# motherboard.net
KiCad netlist of a schematic drawn in EAGLE
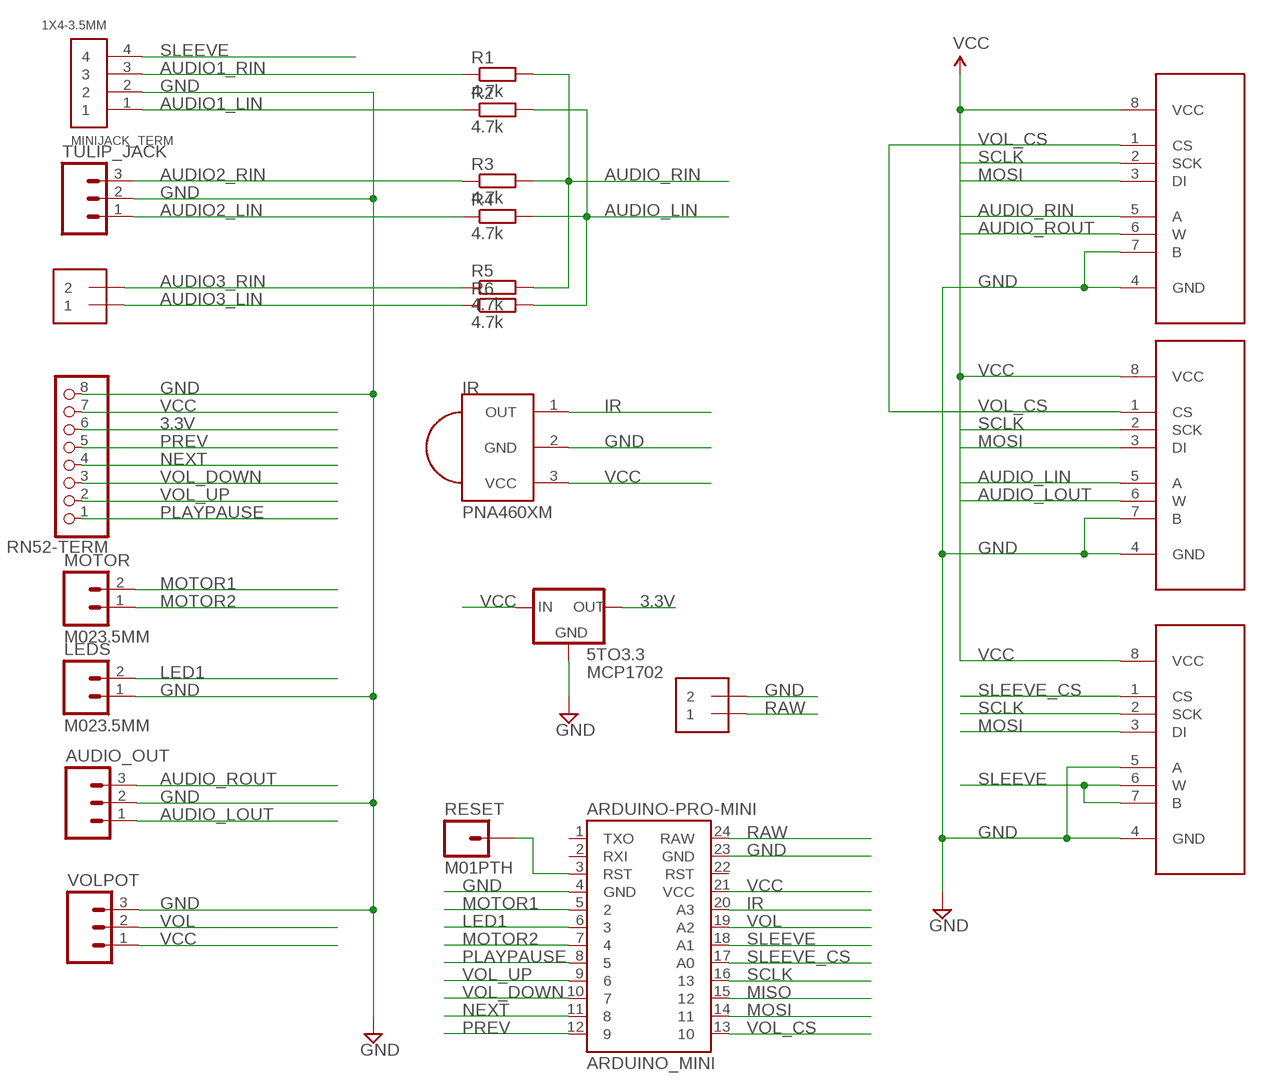
[diagram p0: schematic, sheet 1]

(export (version "E")
  (design (tool "Eeschema 10.0.6"))
  (components
    (comp (ref "5TO3.3")
      (value "MCP1702")
      (footprint "eagle-import:TO92-INLINE")
      (libsource (lib "eagle-import") (part "MCP1700INLINE"))
    )
    (comp (ref "ARDUINO-PRO-MINI")
      (value "ARDUINO_MINI")
      (footprint "eagle-import:ARDUINO_MINI")
      (libsource (lib "eagle-import") (part "ARDUINO_MINI"))
    )
    (comp (ref "AUDIO_OUT")
      (value "M03SCREW")
      (footprint "eagle-import:SCREWTERMINAL-3.5MM-3")
      (libsource (lib "eagle-import") (part "M03SCREW"))
    )
    (comp (ref "BL_AUDIO_TERM")
      (value "1X2-3.5MM")
      (footprint "eagle-import:1X2-3.5MM")
      (libsource (lib "eagle-import") (part "1X2-3.5MM"))
    )
    (comp (ref "DPOT_LFT")
      (value "MCP41XXXDIL")
      (footprint "eagle-import:DIL-08")
      (libsource (lib "eagle-import") (part "MCP41XXXDIL"))
    )
    (comp (ref "DPOT_RGHT")
      (value "MCP41XXXDIL")
      (footprint "eagle-import:DIL-08")
      (libsource (lib "eagle-import") (part "MCP41XXXDIL"))
    )
    (comp (ref "DPOT_SLEEVE")
      (value "MCP41XXXDIL")
      (footprint "eagle-import:DIL-08")
      (libsource (lib "eagle-import") (part "MCP41XXXDIL"))
    )
    (comp (ref "IR")
      (value "PNA460XM")
      (footprint "eagle-import:PNA460XM")
      (libsource (lib "eagle-import") (part "PNA460XM"))
    )
    (comp (ref "LEDS")
      (value "M023.5MM")
      (footprint "eagle-import:SCREWTERMINAL-3.5MM-2")
      (libsource (lib "eagle-import") (part "M023.5MM"))
    )
    (comp (ref "MINIJACK_TERM")
      (value "1X4-3.5MM")
      (footprint "eagle-import:1X04-3.5MM")
      (libsource (lib "eagle-import") (part "1X4-3.5MM"))
    )
    (comp (ref "MOTOR")
      (value "M023.5MM")
      (footprint "eagle-import:SCREWTERMINAL-3.5MM-2")
      (libsource (lib "eagle-import") (part "M023.5MM"))
    )
    (comp (ref "POWER")
      (value "1X2-3.5MM")
      (footprint "eagle-import:1X2-3.5MM")
      (libsource (lib "eagle-import") (part "1X2-3.5MM"))
    )
    (comp (ref "R1")
      (value "4.7k")
      (footprint "eagle-import:0207_10")
      (libsource (lib "eagle-import") (part "R-EU_0207/10"))
    )
    (comp (ref "R2")
      (value "4.7k")
      (footprint "eagle-import:0207_10")
      (libsource (lib "eagle-import") (part "R-EU_0207/10"))
    )
    (comp (ref "R3")
      (value "4.7k")
      (footprint "eagle-import:0207_10")
      (libsource (lib "eagle-import") (part "R-EU_0207/10"))
    )
    (comp (ref "R4")
      (value "4.7k")
      (footprint "eagle-import:0207_10")
      (libsource (lib "eagle-import") (part "R-EU_0207/10"))
    )
    (comp (ref "R5")
      (value "4.7k")
      (footprint "eagle-import:0207_10")
      (libsource (lib "eagle-import") (part "R-EU_0207/10"))
    )
    (comp (ref "R6")
      (value "4.7k")
      (footprint "eagle-import:0207_10")
      (libsource (lib "eagle-import") (part "R-EU_0207/10"))
    )
    (comp (ref "RESET")
      (value "M01PTH")
      (footprint "eagle-import:1X01")
      (libsource (lib "eagle-import") (part "M01PTH"))
    )
    (comp (ref "RN52-TERM")
      (value "PINHD-1X8-3.5MM")
      (footprint "eagle-import:1X08-3.5MM")
      (libsource (lib "eagle-import") (part "PINHD-1X8-3.5MM"))
    )
    (comp (ref "TULIP_JACK")
      (value "M03SCREW")
      (footprint "eagle-import:SCREWTERMINAL-3.5MM-3")
      (libsource (lib "eagle-import") (part "M03SCREW"))
    )
    (comp (ref "VOLPOT")
      (value "M03SCREW")
      (footprint "eagle-import:SCREWTERMINAL-3.5MM-3")
      (libsource (lib "eagle-import") (part "M03SCREW"))
    )
  )
  (nets
    (net (code "1") (name "/3.3V") (class "Default")
      (node (ref "5TO3.3") (pin "3") (pinfunction "OUT_3") (pintype "passive"))
      (node (ref "RN52-TERM") (pin "6") (pinfunction "6_6") (pintype "passive"))
    )
    (net (code "2") (name "/AUDIO1_LIN") (class "Default")
      (node (ref "MINIJACK_TERM") (pin "1") (pinfunction "1_1") (pintype "bidirectional"))
      (node (ref "R2") (pin "1") (pinfunction "1_1") (pintype "passive"))
    )
    (net (code "3") (name "/AUDIO1_RIN") (class "Default")
      (node (ref "MINIJACK_TERM") (pin "3") (pinfunction "3_3") (pintype "bidirectional"))
      (node (ref "R1") (pin "1") (pinfunction "1_1") (pintype "passive"))
    )
    (net (code "4") (name "/AUDIO2_LIN") (class "Default")
      (node (ref "R4") (pin "1") (pinfunction "1_1") (pintype "passive"))
      (node (ref "TULIP_JACK") (pin "1") (pinfunction "1_1") (pintype "passive"))
    )
    (net (code "5") (name "/AUDIO2_RIN") (class "Default")
      (node (ref "R3") (pin "1") (pinfunction "1_1") (pintype "passive"))
      (node (ref "TULIP_JACK") (pin "3") (pinfunction "3_3") (pintype "passive"))
    )
    (net (code "6") (name "/AUDIO3_LIN") (class "Default")
      (node (ref "BL_AUDIO_TERM") (pin "1") (pinfunction "1_1") (pintype "passive"))
      (node (ref "R6") (pin "1") (pinfunction "1_1") (pintype "passive"))
    )
    (net (code "7") (name "/AUDIO3_RIN") (class "Default")
      (node (ref "BL_AUDIO_TERM") (pin "2") (pinfunction "2_2") (pintype "passive"))
      (node (ref "R5") (pin "1") (pinfunction "1_1") (pintype "passive"))
    )
    (net (code "8") (name "/AUDIO_LIN") (class "Default")
      (node (ref "DPOT_LFT") (pin "5") (pinfunction "A_5") (pintype "bidirectional"))
      (node (ref "R2") (pin "2") (pinfunction "2_2") (pintype "passive"))
      (node (ref "R4") (pin "2") (pinfunction "2_2") (pintype "passive"))
      (node (ref "R6") (pin "2") (pinfunction "2_2") (pintype "passive"))
    )
    (net (code "9") (name "/AUDIO_LOUT") (class "Default")
      (node (ref "AUDIO_OUT") (pin "1") (pinfunction "1_1") (pintype "passive"))
      (node (ref "DPOT_LFT") (pin "6") (pinfunction "W_6") (pintype "bidirectional"))
    )
    (net (code "10") (name "/AUDIO_RIN") (class "Default")
      (node (ref "DPOT_RGHT") (pin "5") (pinfunction "A_5") (pintype "bidirectional"))
      (node (ref "R1") (pin "2") (pinfunction "2_2") (pintype "passive"))
      (node (ref "R3") (pin "2") (pinfunction "2_2") (pintype "passive"))
      (node (ref "R5") (pin "2") (pinfunction "2_2") (pintype "passive"))
    )
    (net (code "11") (name "/AUDIO_ROUT") (class "Default")
      (node (ref "AUDIO_OUT") (pin "3") (pinfunction "3_3") (pintype "passive"))
      (node (ref "DPOT_RGHT") (pin "6") (pinfunction "W_6") (pintype "bidirectional"))
    )
    (net (code "12") (name "/IR") (class "Default")
      (node (ref "ARDUINO-PRO-MINI") (pin "20") (pinfunction "A3_20") (pintype "bidirectional"))
      (node (ref "IR") (pin "1") (pinfunction "OUT_1") (pintype "output"))
    )
    (net (code "13") (name "/LED1") (class "Default")
      (node (ref "ARDUINO-PRO-MINI") (pin "6") (pinfunction "3_6") (pintype "bidirectional"))
      (node (ref "LEDS") (pin "2") (pinfunction "2_2") (pintype "passive"))
    )
    (net (code "14") (name "/MISO") (class "Default")
      (node (ref "ARDUINO-PRO-MINI") (pin "15") (pinfunction "12_15") (pintype "bidirectional"))
    )
    (net (code "15") (name "/MOSI") (class "Default")
      (node (ref "ARDUINO-PRO-MINI") (pin "14") (pinfunction "11_14") (pintype "bidirectional"))
      (node (ref "DPOT_LFT") (pin "3") (pinfunction "DI_3") (pintype "bidirectional"))
      (node (ref "DPOT_RGHT") (pin "3") (pinfunction "DI_3") (pintype "bidirectional"))
      (node (ref "DPOT_SLEEVE") (pin "3") (pinfunction "DI_3") (pintype "bidirectional"))
    )
    (net (code "16") (name "/MOTOR1") (class "Default")
      (node (ref "ARDUINO-PRO-MINI") (pin "5") (pinfunction "2_5") (pintype "bidirectional"))
      (node (ref "MOTOR") (pin "2") (pinfunction "2_2") (pintype "passive"))
    )
    (net (code "17") (name "/MOTOR2") (class "Default")
      (node (ref "ARDUINO-PRO-MINI") (pin "7") (pinfunction "4_7") (pintype "bidirectional"))
      (node (ref "MOTOR") (pin "1") (pinfunction "1_1") (pintype "passive"))
    )
    (net (code "18") (name "/NEXT") (class "Default")
      (node (ref "ARDUINO-PRO-MINI") (pin "11") (pinfunction "8_11") (pintype "bidirectional"))
      (node (ref "RN52-TERM") (pin "4") (pinfunction "4_4") (pintype "passive"))
    )
    (net (code "19") (name "/PLAYPAUSE") (class "Default")
      (node (ref "ARDUINO-PRO-MINI") (pin "8") (pinfunction "5_8") (pintype "bidirectional"))
      (node (ref "RN52-TERM") (pin "1") (pinfunction "1_1") (pintype "passive"))
    )
    (net (code "20") (name "/PREV") (class "Default")
      (node (ref "ARDUINO-PRO-MINI") (pin "12") (pinfunction "9_12") (pintype "bidirectional"))
      (node (ref "RN52-TERM") (pin "5") (pinfunction "5_5") (pintype "passive"))
    )
    (net (code "21") (name "/RAW") (class "Default")
      (node (ref "ARDUINO-PRO-MINI") (pin "24") (pinfunction "RAW_24") (pintype "bidirectional"))
      (node (ref "POWER") (pin "1") (pinfunction "1_1") (pintype "passive"))
    )
    (net (code "22") (name "/SCLK") (class "Default")
      (node (ref "ARDUINO-PRO-MINI") (pin "16") (pinfunction "13_16") (pintype "bidirectional"))
      (node (ref "DPOT_LFT") (pin "2") (pinfunction "SCK_2") (pintype "bidirectional"))
      (node (ref "DPOT_RGHT") (pin "2") (pinfunction "SCK_2") (pintype "bidirectional"))
      (node (ref "DPOT_SLEEVE") (pin "2") (pinfunction "SCK_2") (pintype "bidirectional"))
    )
    (net (code "23") (name "/SLEEVE") (class "Default")
      (node (ref "ARDUINO-PRO-MINI") (pin "18") (pinfunction "A1_18") (pintype "bidirectional"))
      (node (ref "DPOT_SLEEVE") (pin "6") (pinfunction "W_6") (pintype "bidirectional"))
      (node (ref "DPOT_SLEEVE") (pin "7") (pinfunction "B_7") (pintype "bidirectional"))
      (node (ref "MINIJACK_TERM") (pin "4") (pinfunction "4_4") (pintype "bidirectional"))
    )
    (net (code "24") (name "/SLEEVE_CS") (class "Default")
      (node (ref "ARDUINO-PRO-MINI") (pin "17") (pinfunction "A0_17") (pintype "bidirectional"))
      (node (ref "DPOT_SLEEVE") (pin "1") (pinfunction "CS_1") (pintype "bidirectional"))
    )
    (net (code "25") (name "/VOL") (class "Default")
      (node (ref "ARDUINO-PRO-MINI") (pin "19") (pinfunction "A2_19") (pintype "bidirectional"))
      (node (ref "VOLPOT") (pin "2") (pinfunction "2_2") (pintype "passive"))
    )
    (net (code "26") (name "/VOL_CS") (class "Default")
      (node (ref "ARDUINO-PRO-MINI") (pin "13") (pinfunction "10_13") (pintype "bidirectional"))
      (node (ref "DPOT_LFT") (pin "1") (pinfunction "CS_1") (pintype "bidirectional"))
      (node (ref "DPOT_RGHT") (pin "1") (pinfunction "CS_1") (pintype "bidirectional"))
    )
    (net (code "27") (name "/VOL_DOWN") (class "Default")
      (node (ref "ARDUINO-PRO-MINI") (pin "10") (pinfunction "7_10") (pintype "bidirectional"))
      (node (ref "RN52-TERM") (pin "3") (pinfunction "3_3") (pintype "passive"))
    )
    (net (code "28") (name "/VOL_UP") (class "Default")
      (node (ref "ARDUINO-PRO-MINI") (pin "9") (pinfunction "6_9") (pintype "bidirectional"))
      (node (ref "RN52-TERM") (pin "2") (pinfunction "2_2") (pintype "passive"))
    )
    (net (code "29") (name "GND") (class "Default")
      (node (ref "5TO3.3") (pin "1") (pinfunction "GND_1") (pintype "input"))
      (node (ref "ARDUINO-PRO-MINI") (pin "23") (pinfunction "GND_23") (pintype "bidirectional"))
      (node (ref "ARDUINO-PRO-MINI") (pin "4") (pinfunction "GND_4") (pintype "bidirectional"))
      (node (ref "AUDIO_OUT") (pin "2") (pinfunction "2_2") (pintype "passive"))
      (node (ref "DPOT_LFT") (pin "4") (pinfunction "GND_4") (pintype "bidirectional"))
      (node (ref "DPOT_LFT") (pin "7") (pinfunction "B_7") (pintype "bidirectional"))
      (node (ref "DPOT_RGHT") (pin "4") (pinfunction "GND_4") (pintype "bidirectional"))
      (node (ref "DPOT_RGHT") (pin "7") (pinfunction "B_7") (pintype "bidirectional"))
      (node (ref "DPOT_SLEEVE") (pin "4") (pinfunction "GND_4") (pintype "bidirectional"))
      (node (ref "DPOT_SLEEVE") (pin "5") (pinfunction "A_5") (pintype "bidirectional"))
      (node (ref "IR") (pin "2") (pinfunction "GND_2") (pintype "power_in"))
      (node (ref "LEDS") (pin "1") (pinfunction "1_1") (pintype "passive"))
      (node (ref "MINIJACK_TERM") (pin "2") (pinfunction "2_2") (pintype "bidirectional"))
      (node (ref "POWER") (pin "2") (pinfunction "2_2") (pintype "passive"))
      (node (ref "RN52-TERM") (pin "8") (pinfunction "8_8") (pintype "passive"))
      (node (ref "TULIP_JACK") (pin "2") (pinfunction "2_2") (pintype "passive"))
      (node (ref "VOLPOT") (pin "3") (pinfunction "3_3") (pintype "passive"))
    )
    (net (code "30") (name "Net-(ARDUINO-PRO-MINI-RST-Pad3)") (class "Default")
      (node (ref "ARDUINO-PRO-MINI") (pin "3") (pinfunction "RST_3") (pintype "bidirectional"))
      (node (ref "RESET") (pin "1") (pinfunction "1_1") (pintype "passive"))
    )
    (net (code "31") (name "VCC") (class "Default")
      (node (ref "5TO3.3") (pin "2") (pinfunction "IN_2") (pintype "input"))
      (node (ref "ARDUINO-PRO-MINI") (pin "21") (pinfunction "VCC_21") (pintype "bidirectional"))
      (node (ref "DPOT_LFT") (pin "8") (pinfunction "VCC_8") (pintype "bidirectional"))
      (node (ref "DPOT_RGHT") (pin "8") (pinfunction "VCC_8") (pintype "bidirectional"))
      (node (ref "DPOT_SLEEVE") (pin "8") (pinfunction "VCC_8") (pintype "bidirectional"))
      (node (ref "IR") (pin "3") (pinfunction "VCC_3") (pintype "power_in"))
      (node (ref "RN52-TERM") (pin "7") (pinfunction "7_7") (pintype "passive"))
      (node (ref "VOLPOT") (pin "1") (pinfunction "1_1") (pintype "passive"))
    )
    (net (code "32") (name "unconnected-(ARDUINO-PRO-MINI-RST-Pad22)") (class "Default")
      (node (ref "ARDUINO-PRO-MINI") (pin "22") (pinfunction "RST_22") (pintype "bidirectional"))
    )
    (net (code "33") (name "unconnected-(ARDUINO-PRO-MINI-RXI-Pad2)") (class "Default")
      (node (ref "ARDUINO-PRO-MINI") (pin "2") (pinfunction "RXI_2") (pintype "bidirectional"))
    )
    (net (code "34") (name "unconnected-(ARDUINO-PRO-MINI-TXO-Pad1)") (class "Default")
      (node (ref "ARDUINO-PRO-MINI") (pin "1") (pinfunction "TXO_1") (pintype "bidirectional"))
    )
  )
)
